# Pont_en_H.net
KiCad netlist of a schematic drawn in Altium Designer
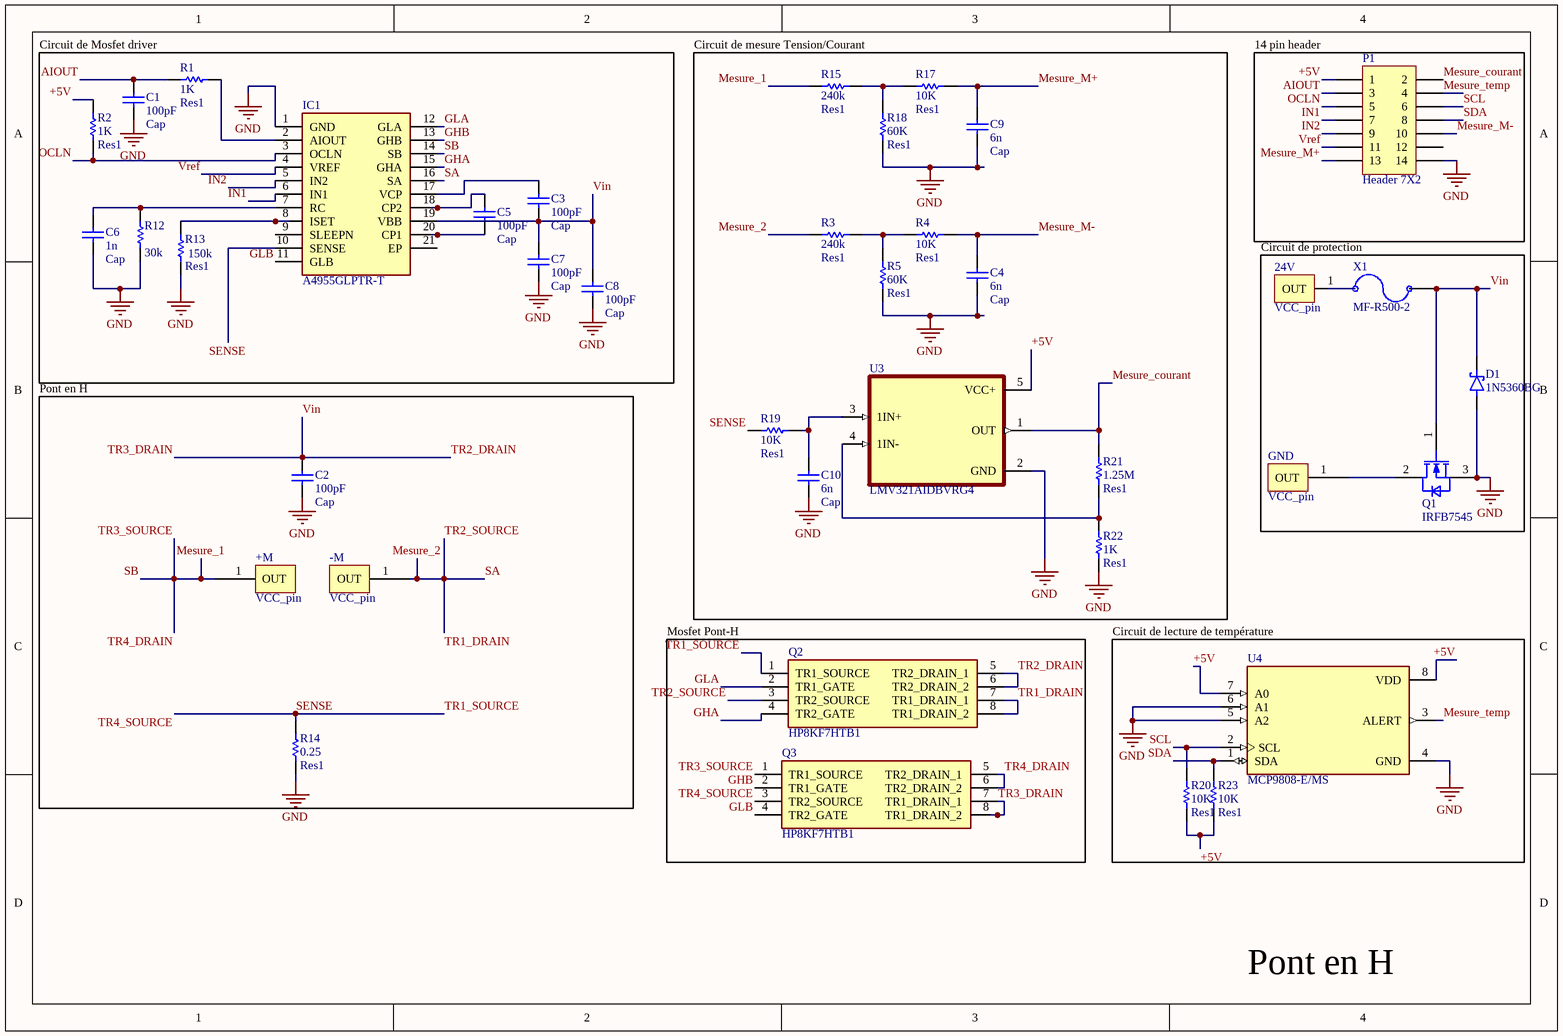
[diagram p0: Pont en H.SchDoc]

(export (version "E")
  (design (tool "Eeschema 10.0.6"))
  (components
    (comp (ref "+M")
      (value "VCC_pin")
      (footprint "A25_Projet_conv_CC_Library:banana_connector")
      (libsource (lib "") (part "VCC_pin_1"))
    )
    (comp (ref "-M")
      (value "VCC_pin")
      (footprint "banana_connector")
      (libsource (lib "24V_PIN") (part "VCC_pin"))
    )
    (comp (ref "24V")
      (value "VCC_pin")
      (footprint "banana_connector")
      (libsource (lib "24V_PIN") (part "VCC_pin"))
    )
    (comp (ref "C1")
      (value "Cap")
      (footprint "RAD-0.3")
      (description "Capacitor")
      (fields (field (name "ALTIUM_VALUE") "100pF") (field (name "PUBLISHER") "Altium Limited"))
      (libsource (lib "Miscellaneous Devices") (part "Cap"))
    )
    (comp (ref "C2")
      (value "Cap")
      (footprint "RAD-0.3")
      (description "Capacitor")
      (fields (field (name "ALTIUM_VALUE") "100pF") (field (name "PUBLISHER") "Altium Limited"))
      (libsource (lib "Miscellaneous Devices") (part "Cap"))
    )
    (comp (ref "C3")
      (value "Cap")
      (footprint "RAD-0.3")
      (description "Capacitor")
      (fields (field (name "ALTIUM_VALUE") "100pF") (field (name "PUBLISHER") "Altium Limited"))
      (libsource (lib "Miscellaneous Devices") (part "Cap"))
    )
    (comp (ref "C4")
      (value "Cap")
      (footprint "RAD-0.3")
      (description "Capacitor")
      (fields (field (name "ALTIUM_VALUE") "6n") (field (name "PUBLISHER") "Altium Limited"))
      (libsource (lib "Miscellaneous Devices") (part "Cap"))
    )
    (comp (ref "C5")
      (value "Cap")
      (footprint "RAD-0.3")
      (description "Capacitor")
      (fields (field (name "ALTIUM_VALUE") "100pF") (field (name "PUBLISHER") "Altium Limited"))
      (libsource (lib "Miscellaneous Devices") (part "Cap"))
    )
    (comp (ref "C6")
      (value "Cap")
      (footprint "RAD-0.3")
      (description "Capacitor")
      (fields (field (name "ALTIUM_VALUE") "1n") (field (name "PUBLISHER") "Altium Limited"))
      (libsource (lib "Miscellaneous Devices") (part "Cap"))
    )
    (comp (ref "C7")
      (value "Cap")
      (footprint "RAD-0.3")
      (description "Capacitor")
      (fields (field (name "ALTIUM_VALUE") "100pF") (field (name "PUBLISHER") "Altium Limited"))
      (libsource (lib "Miscellaneous Devices") (part "Cap"))
    )
    (comp (ref "C8")
      (value "Cap")
      (footprint "RAD-0.3")
      (description "Capacitor")
      (fields (field (name "ALTIUM_VALUE") "100pF") (field (name "PUBLISHER") "Altium Limited"))
      (libsource (lib "Miscellaneous Devices") (part "Cap"))
    )
    (comp (ref "C9")
      (value "Cap")
      (footprint "Miscellaneous Devices:C1206")
      (description "Capacitor")
      (fields (field (name "ALTIUM_VALUE") "6n") (field (name "PUBLISHER") "Altium Limited"))
      (libsource (lib "Miscellaneous Devices") (part "Cap"))
    )
    (comp (ref "C10")
      (value "Cap")
      (footprint "RAD-0.3")
      (description "Capacitor")
      (fields (field (name "ALTIUM_VALUE") "6n") (field (name "PUBLISHER") "Altium Limited"))
      (libsource (lib "Miscellaneous Devices") (part "Cap"))
    )
    (comp (ref "D1")
      (value "1N5360BG")
      (footprint "DIOAD1543W101L863D368")
      (fields (field (name "MF") "{'manufacturer': u'onsemi'}"))
      (libsource (lib "A25_Projet_conv_CC_Library") (part "1N5360BG"))
    )
    (comp (ref "GND")
      (value "VCC_pin")
      (footprint "banana_connector")
      (libsource (lib "24V_PIN") (part "VCC_pin"))
    )
    (comp (ref "IC1")
      (value "A4955GLPTR-T")
      (footprint "A4405KLPTRT")
      (description "Integrated Circuit")
      (fields (field (name "MOUSER PART NUMBER") "250-A4955GLPTR-T"))
      (libsource (lib "A25_Projet_conv_CC_Library") (part "A4955GLPTR-T"))
    )
    (comp (ref "P1")
      (value "Header 7X2")
      (footprint "HDR2X7")
      (description "Header, 7-Pin, Dual row")
      (fields (field (name "PUBLISHER") "Altium Limited"))
      (libsource (lib "Miscellaneous Connectors") (part "Header 7X2"))
    )
    (comp (ref "Q1")
      (value "IRFB7545")
      (footprint "IFX-PG-TO220-3-904")
      (fields (field (name "MANUFACTURER") "Infineon Technologies"))
      (libsource (lib "A25_Projet_conv_CC_Library") (part "IRFB7545"))
    )
    (comp (ref "Q2")
      (value "HP8KF7HTB1")
      (footprint "HP8KC6TB1")
      (description "MOSFET (N-Channel)")
      (libsource (lib "A25_Projet_conv_CC_Library") (part "HP8KF7HTB1"))
    )
    (comp (ref "Q3")
      (value "HP8KF7HTB1")
      (footprint "HP8KC6TB1")
      (description "MOSFET (N-Channel)")
      (libsource (lib "A25_Projet_conv_CC_Library") (part "HP8KF7HTB1"))
    )
    (comp (ref "R1")
      (value "Res1")
      (footprint "AXIAL-0.3")
      (description "Resistor")
      (fields (field (name "ALTIUM_VALUE") "1K") (field (name "PUBLISHER") "Altium Limited"))
      (libsource (lib "Miscellaneous Devices") (part "Res1"))
    )
    (comp (ref "R2")
      (value "Res1")
      (footprint "AXIAL-0.3")
      (description "Resistor")
      (fields (field (name "ALTIUM_VALUE") "1K") (field (name "PUBLISHER") "Altium Limited"))
      (libsource (lib "Miscellaneous Devices") (part "Res1"))
    )
    (comp (ref "R3")
      (value "Res1")
      (footprint "AXIAL-0.3")
      (description "Resistor")
      (fields (field (name "ALTIUM_VALUE") "240k") (field (name "PUBLISHER") "Altium Limited"))
      (libsource (lib "Miscellaneous Devices") (part "Res1"))
    )
    (comp (ref "R4")
      (value "Res1")
      (footprint "AXIAL-0.3")
      (description "Resistor")
      (fields (field (name "ALTIUM_VALUE") "10K") (field (name "PUBLISHER") "Altium Limited"))
      (libsource (lib "Miscellaneous Devices") (part "Res1"))
    )
    (comp (ref "R5")
      (value "Res1")
      (footprint "AXIAL-0.3")
      (description "Resistor")
      (fields (field (name "ALTIUM_VALUE") "60K") (field (name "PUBLISHER") "Altium Limited"))
      (libsource (lib "Miscellaneous Devices") (part "Res1"))
    )
    (comp (ref "R12")
      (value "30k")
      (footprint "AXIAL-0.3")
      (description "Resistor")
      (fields (field (name "PUBLISHER") "Altium Limited"))
      (libsource (lib "Miscellaneous Devices") (part "Res1"))
    )
    (comp (ref "R13")
      (value "Res1")
      (footprint "AXIAL-0.3")
      (description "Resistor")
      (fields (field (name "ALTIUM_VALUE") "150k") (field (name "PUBLISHER") "Altium Limited"))
      (libsource (lib "Miscellaneous Devices") (part "Res1"))
    )
    (comp (ref "R14")
      (value "Res1")
      (footprint "AXIAL-0.3")
      (description "Resistor")
      (fields (field (name "ALTIUM_VALUE") "0.25") (field (name "PUBLISHER") "Altium Limited"))
      (libsource (lib "Miscellaneous Devices") (part "Res1"))
    )
    (comp (ref "R15")
      (value "Res1")
      (footprint "Miscellaneous Devices:AXIAL-0.3")
      (description "Resistor")
      (fields (field (name "ALTIUM_VALUE") "240k") (field (name "PUBLISHER") "Altium Limited"))
      (libsource (lib "Miscellaneous Devices") (part "Res1"))
    )
    (comp (ref "R17")
      (value "Res1")
      (footprint "Miscellaneous Devices:AXIAL-0.3")
      (description "Resistor")
      (fields (field (name "ALTIUM_VALUE") "10K") (field (name "PUBLISHER") "Altium Limited"))
      (libsource (lib "Miscellaneous Devices") (part "Res1"))
    )
    (comp (ref "R18")
      (value "Res1")
      (footprint "AXIAL-0.3")
      (description "Resistor")
      (fields (field (name "ALTIUM_VALUE") "60K") (field (name "PUBLISHER") "Altium Limited"))
      (libsource (lib "Miscellaneous Devices") (part "Res1"))
    )
    (comp (ref "R19")
      (value "Res1")
      (footprint "AXIAL-0.3")
      (description "Resistor")
      (fields (field (name "ALTIUM_VALUE") "10K") (field (name "PUBLISHER") "Altium Limited"))
      (libsource (lib "Miscellaneous Devices") (part "Res1"))
    )
    (comp (ref "R20")
      (value "Res1")
      (footprint "AXIAL-0.3")
      (description "Resistor")
      (fields (field (name "ALTIUM_VALUE") "10K") (field (name "PUBLISHER") "Altium Limited"))
      (libsource (lib "Miscellaneous Devices") (part "Res1"))
    )
    (comp (ref "R21")
      (value "Res1")
      (footprint "AXIAL-0.3")
      (description "Resistor")
      (fields (field (name "ALTIUM_VALUE") "1.25M") (field (name "PUBLISHER") "Altium Limited"))
      (libsource (lib "Miscellaneous Devices") (part "Res1"))
    )
    (comp (ref "R22")
      (value "Res1")
      (footprint "AXIAL-0.3")
      (description "Resistor")
      (fields (field (name "ALTIUM_VALUE") "1K") (field (name "PUBLISHER") "Altium Limited"))
      (libsource (lib "Miscellaneous Devices") (part "Res1"))
    )
    (comp (ref "R23")
      (value "Res1")
      (footprint "AXIAL-0.3")
      (description "Resistor")
      (fields (field (name "ALTIUM_VALUE") "10K") (field (name "PUBLISHER") "Altium Limited"))
      (libsource (lib "Miscellaneous Devices") (part "Res1"))
    )
    (comp (ref "U3")
      (value "LMV321AIDBVRG4")
      (footprint "SOT95P280X145-5N")
      (fields (field (name "MF") "Texas Instruments") (field (name "MP") "LMV321IDBVRG4"))
      (libsource (lib "A25_Projet_conv_CC_Library") (part "LMV321AIDBVRG4"))
    )
    (comp (ref "U4")
      (value "MCP9808-E/MS")
      (footprint "SOP65P490X110-8N")
      (fields (field (name "MF") "Microchip"))
      (libsource (lib "A25_Projet_conv_CC_Library") (part "MCP9808-E/MS"))
    )
    (comp (ref "X1")
      (value "MF-R500-2")
      (footprint "MF-R500-2")
      (libsource (lib "A25_Projet_conv_CC_Library") (part "MF-R500-2"))
    )
  )
  (nets
    (net (code "1") (name "/+5V") (class "Default")
      (node (ref "P1") (pin "1") (pinfunction "1_1") (pintype "passive"))
      (node (ref "R2") (pin "2") (pinfunction "2_2") (pintype "passive"))
      (node (ref "R20") (pin "1") (pinfunction "1_1") (pintype "passive"))
      (node (ref "R23") (pin "1") (pinfunction "1_1") (pintype "passive"))
      (node (ref "U3") (pin "5") (pinfunction "VCC+_5") (pintype "power_in"))
      (node (ref "U4") (pin "7") (pinfunction "A0_7") (pintype "input"))
      (node (ref "U4") (pin "8") (pinfunction "VDD_8") (pintype "power_in"))
    )
    (net (code "2") (name "/AIOUT") (class "Default")
      (node (ref "C1") (pin "2") (pinfunction "2_2") (pintype "passive"))
      (node (ref "P1") (pin "3") (pinfunction "3_3") (pintype "passive"))
      (node (ref "R1") (pin "2") (pinfunction "2_2") (pintype "passive"))
    )
    (net (code "3") (name "/GHA") (class "Default")
      (node (ref "IC1") (pin "15") (pinfunction "GHA_15") (pintype "passive"))
      (node (ref "Q2") (pin "4") (pinfunction "TR2_GATE_4") (pintype "passive"))
    )
    (net (code "4") (name "/GHB") (class "Default")
      (node (ref "IC1") (pin "13") (pinfunction "GHB_13") (pintype "passive"))
      (node (ref "Q3") (pin "2") (pinfunction "TR1_GATE_2") (pintype "passive"))
    )
    (net (code "5") (name "/GLA") (class "Default")
      (node (ref "IC1") (pin "12") (pinfunction "GLA_12") (pintype "passive"))
      (node (ref "Q2") (pin "2") (pinfunction "TR1_GATE_2") (pintype "passive"))
    )
    (net (code "6") (name "/GLB") (class "Default")
      (node (ref "IC1") (pin "11") (pinfunction "GLB_11") (pintype "passive"))
      (node (ref "Q3") (pin "4") (pinfunction "TR2_GATE_4") (pintype "passive"))
    )
    (net (code "7") (name "/IN1") (class "Default")
      (node (ref "IC1") (pin "6") (pinfunction "IN1_6") (pintype "passive"))
      (node (ref "P1") (pin "7") (pinfunction "7_7") (pintype "passive"))
    )
    (net (code "8") (name "/IN2") (class "Default")
      (node (ref "IC1") (pin "5") (pinfunction "IN2_5") (pintype "passive"))
      (node (ref "P1") (pin "9") (pinfunction "9_9") (pintype "passive"))
    )
    (net (code "9") (name "/Mesure_1") (class "Default")
      (node (ref "+M") (pin "1") (pinfunction "OUT_1") (pintype "passive"))
      (node (ref "IC1") (pin "14") (pinfunction "SB_14") (pintype "passive"))
      (node (ref "Q3") (pin "1") (pinfunction "TR1_SOURCE_1") (pintype "passive"))
      (node (ref "Q3") (pin "5") (pinfunction "TR2_DRAIN_1_5") (pintype "passive"))
      (node (ref "Q3") (pin "6") (pinfunction "TR2_DRAIN_2_6") (pintype "passive"))
      (node (ref "R15") (pin "1") (pinfunction "1_1") (pintype "passive"))
    )
    (net (code "10") (name "/Mesure_2") (class "Default")
      (node (ref "-M") (pin "1") (pinfunction "OUT_1") (pintype "passive"))
      (node (ref "IC1") (pin "16") (pinfunction "SA_16") (pintype "passive"))
      (node (ref "Q2") (pin "3") (pinfunction "TR2_SOURCE_3") (pintype "passive"))
      (node (ref "Q2") (pin "7") (pinfunction "TR1_DRAIN_1_7") (pintype "passive"))
      (node (ref "Q2") (pin "8") (pinfunction "TR1_DRAIN_2_8") (pintype "passive"))
      (node (ref "R3") (pin "1") (pinfunction "1_1") (pintype "passive"))
    )
    (net (code "11") (name "/Mesure_M+") (class "Default")
      (node (ref "C9") (pin "2") (pinfunction "2_2") (pintype "passive"))
      (node (ref "P1") (pin "13") (pinfunction "13_13") (pintype "passive"))
      (node (ref "R17") (pin "2") (pinfunction "2_2") (pintype "passive"))
    )
    (net (code "12") (name "/Mesure_M-") (class "Default")
      (node (ref "C4") (pin "2") (pinfunction "2_2") (pintype "passive"))
      (node (ref "P1") (pin "10") (pinfunction "10_10") (pintype "passive"))
      (node (ref "R4") (pin "2") (pinfunction "2_2") (pintype "passive"))
    )
    (net (code "13") (name "/Mesure_courant") (class "Default")
      (node (ref "P1") (pin "2") (pinfunction "2_2") (pintype "passive"))
      (node (ref "R21") (pin "2") (pinfunction "2_2") (pintype "passive"))
      (node (ref "U3") (pin "1") (pinfunction "OUT_1") (pintype "output"))
    )
    (net (code "14") (name "/Mesure_temp") (class "Default")
      (node (ref "P1") (pin "4") (pinfunction "4_4") (pintype "passive"))
      (node (ref "U4") (pin "3") (pinfunction "ALERT_3") (pintype "output"))
    )
    (net (code "15") (name "/OCLN") (class "Default")
      (node (ref "IC1") (pin "3") (pinfunction "OCLN_3") (pintype "passive"))
      (node (ref "P1") (pin "5") (pinfunction "5_5") (pintype "passive"))
      (node (ref "R2") (pin "1") (pinfunction "1_1") (pintype "passive"))
    )
    (net (code "16") (name "/SCL") (class "Default")
      (node (ref "P1") (pin "6") (pinfunction "6_6") (pintype "passive"))
      (node (ref "R20") (pin "2") (pinfunction "2_2") (pintype "passive"))
      (node (ref "U4") (pin "2") (pinfunction "SCL_2") (pintype "input"))
    )
    (net (code "17") (name "/SDA") (class "Default")
      (node (ref "P1") (pin "8") (pinfunction "8_8") (pintype "passive"))
      (node (ref "R23") (pin "2") (pinfunction "2_2") (pintype "passive"))
      (node (ref "U4") (pin "1") (pinfunction "SDA_1") (pintype "bidirectional"))
    )
    (net (code "18") (name "/SENSE") (class "Default")
      (node (ref "IC1") (pin "10") (pinfunction "SENSE_10") (pintype "passive"))
      (node (ref "Q2") (pin "1") (pinfunction "TR1_SOURCE_1") (pintype "passive"))
      (node (ref "Q3") (pin "3") (pinfunction "TR2_SOURCE_3") (pintype "passive"))
      (node (ref "R14") (pin "2") (pinfunction "2_2") (pintype "passive"))
      (node (ref "R19") (pin "1") (pinfunction "1_1") (pintype "passive"))
    )
    (net (code "19") (name "/TR2_DRAIN") (class "Default")
      (node (ref "C2") (pin "2") (pinfunction "2_2") (pintype "passive"))
      (node (ref "C3") (pin "1") (pinfunction "1_1") (pintype "passive"))
      (node (ref "C7") (pin "2") (pinfunction "2_2") (pintype "passive"))
      (node (ref "C8") (pin "2") (pinfunction "2_2") (pintype "passive"))
      (node (ref "D1") (pin "1") (pinfunction "K_1") (pintype "passive"))
      (node (ref "IC1") (pin "19") (pinfunction "VBB_19") (pintype "passive"))
      (node (ref "Q1") (pin "1") (pinfunction "GATE_1") (pintype "passive"))
      (node (ref "Q2") (pin "5") (pinfunction "TR2_DRAIN_1_5") (pintype "passive"))
      (node (ref "Q2") (pin "6") (pinfunction "TR2_DRAIN_2_6") (pintype "passive"))
      (node (ref "Q3") (pin "7") (pinfunction "TR1_DRAIN_1_7") (pintype "passive"))
      (node (ref "Q3") (pin "8") (pinfunction "TR1_DRAIN_2_8") (pintype "passive"))
      (node (ref "X1") (pin "2") (pinfunction "2_2") (pintype "passive"))
    )
    (net (code "20") (name "/Vref") (class "Default")
      (node (ref "IC1") (pin "4") (pinfunction "VREF_4") (pintype "passive"))
      (node (ref "P1") (pin "11") (pinfunction "11_11") (pintype "passive"))
    )
    (net (code "21") (name "GND") (class "Default")
      (node (ref "C1") (pin "1") (pinfunction "1_1") (pintype "passive"))
      (node (ref "C10") (pin "1") (pinfunction "1_1") (pintype "passive"))
      (node (ref "C2") (pin "1") (pinfunction "1_1") (pintype "passive"))
      (node (ref "C4") (pin "1") (pinfunction "1_1") (pintype "passive"))
      (node (ref "C6") (pin "1") (pinfunction "1_1") (pintype "passive"))
      (node (ref "C7") (pin "1") (pinfunction "1_1") (pintype "passive"))
      (node (ref "C8") (pin "1") (pinfunction "1_1") (pintype "passive"))
      (node (ref "C9") (pin "1") (pinfunction "1_1") (pintype "passive"))
      (node (ref "D1") (pin "2") (pinfunction "A_2") (pintype "passive"))
      (node (ref "IC1") (pin "1") (pinfunction "GND_1") (pintype "passive"))
      (node (ref "P1") (pin "14") (pinfunction "14_14") (pintype "passive"))
      (node (ref "Q1") (pin "3") (pinfunction "SOURCE_3") (pintype "passive"))
      (node (ref "R12") (pin "1") (pinfunction "1_1") (pintype "passive"))
      (node (ref "R13") (pin "1") (pinfunction "1_1") (pintype "passive"))
      (node (ref "R14") (pin "1") (pinfunction "1_1") (pintype "passive"))
      (node (ref "R18") (pin "1") (pinfunction "1_1") (pintype "passive"))
      (node (ref "R22") (pin "1") (pinfunction "1_1") (pintype "passive"))
      (node (ref "R5") (pin "1") (pinfunction "1_1") (pintype "passive"))
      (node (ref "U3") (pin "2") (pinfunction "GND_2") (pintype "power_in"))
      (node (ref "U4") (pin "4") (pinfunction "GND_4") (pintype "power_in"))
      (node (ref "U4") (pin "5") (pinfunction "A2_5") (pintype "input"))
      (node (ref "U4") (pin "6") (pinfunction "A1_6") (pintype "input"))
    )
    (net (code "22") (name "Net-(24V-OUT)") (class "Default")
      (node (ref "24V") (pin "1") (pinfunction "OUT_1") (pintype "passive"))
      (node (ref "X1") (pin "1") (pinfunction "1_1") (pintype "passive"))
    )
    (net (code "23") (name "Net-(GND-OUT)") (class "Default")
      (node (ref "GND") (pin "1") (pinfunction "OUT_1") (pintype "passive"))
      (node (ref "Q1") (pin "2") (pinfunction "DRAIN_2") (pintype "passive"))
    )
    (net (code "24") (name "Net-(IC1-AIOUT)") (class "Default")
      (node (ref "IC1") (pin "2") (pinfunction "AIOUT_2") (pintype "passive"))
      (node (ref "R1") (pin "1") (pinfunction "1_1") (pintype "passive"))
    )
    (net (code "25") (name "Net-(IC1-CP1)") (class "Default")
      (node (ref "C5") (pin "1") (pinfunction "1_1") (pintype "passive"))
      (node (ref "IC1") (pin "20") (pinfunction "CP1_20") (pintype "passive"))
    )
    (net (code "26") (name "Net-(IC1-CP2)") (class "Default")
      (node (ref "C5") (pin "2") (pinfunction "2_2") (pintype "passive"))
      (node (ref "IC1") (pin "18") (pinfunction "CP2_18") (pintype "passive"))
    )
    (net (code "27") (name "Net-(IC1-ISET)") (class "Default")
      (node (ref "IC1") (pin "8") (pinfunction "ISET_8") (pintype "passive"))
      (node (ref "R13") (pin "2") (pinfunction "2_2") (pintype "passive"))
    )
    (net (code "28") (name "Net-(IC1-RC)") (class "Default")
      (node (ref "C6") (pin "2") (pinfunction "2_2") (pintype "passive"))
      (node (ref "IC1") (pin "7") (pinfunction "RC_7") (pintype "passive"))
      (node (ref "R12") (pin "2") (pinfunction "2_2") (pintype "passive"))
    )
    (net (code "29") (name "Net-(IC1-VCP)") (class "Default")
      (node (ref "C3") (pin "2") (pinfunction "2_2") (pintype "passive"))
      (node (ref "IC1") (pin "17") (pinfunction "VCP_17") (pintype "passive"))
    )
    (net (code "30") (name "Net-(R3-Pad2)") (class "Default")
      (node (ref "R3") (pin "2") (pinfunction "2_2") (pintype "passive"))
      (node (ref "R4") (pin "1") (pinfunction "1_1") (pintype "passive"))
      (node (ref "R5") (pin "2") (pinfunction "2_2") (pintype "passive"))
    )
    (net (code "31") (name "Net-(R15-Pad2)") (class "Default")
      (node (ref "R15") (pin "2") (pinfunction "2_2") (pintype "passive"))
      (node (ref "R17") (pin "1") (pinfunction "1_1") (pintype "passive"))
      (node (ref "R18") (pin "2") (pinfunction "2_2") (pintype "passive"))
    )
    (net (code "32") (name "Net-(U3-1IN+)") (class "Default")
      (node (ref "C10") (pin "2") (pinfunction "2_2") (pintype "passive"))
      (node (ref "R19") (pin "2") (pinfunction "2_2") (pintype "passive"))
      (node (ref "U3") (pin "3") (pinfunction "1IN+_3") (pintype "input"))
    )
    (net (code "33") (name "Net-(U3-1IN-)") (class "Default")
      (node (ref "R21") (pin "1") (pinfunction "1_1") (pintype "passive"))
      (node (ref "R22") (pin "2") (pinfunction "2_2") (pintype "passive"))
      (node (ref "U3") (pin "4") (pinfunction "1IN-_4") (pintype "input"))
    )
    (net (code "34") (name "unconnected-(IC1-EP-Pad21)") (class "Default")
      (node (ref "IC1") (pin "21") (pinfunction "EP_21") (pintype "passive"))
    )
    (net (code "35") (name "unconnected-(IC1-SLEEPN-Pad9)") (class "Default")
      (node (ref "IC1") (pin "9") (pinfunction "SLEEPN_9") (pintype "passive"))
    )
    (net (code "36") (name "unconnected-(P1-Pad12)") (class "Default")
      (node (ref "P1") (pin "12") (pinfunction "12_12") (pintype "passive"))
    )
  )
)
